# IO-testing-mezzanine.net
KiCad netlist of a schematic drawn in Altium Designer
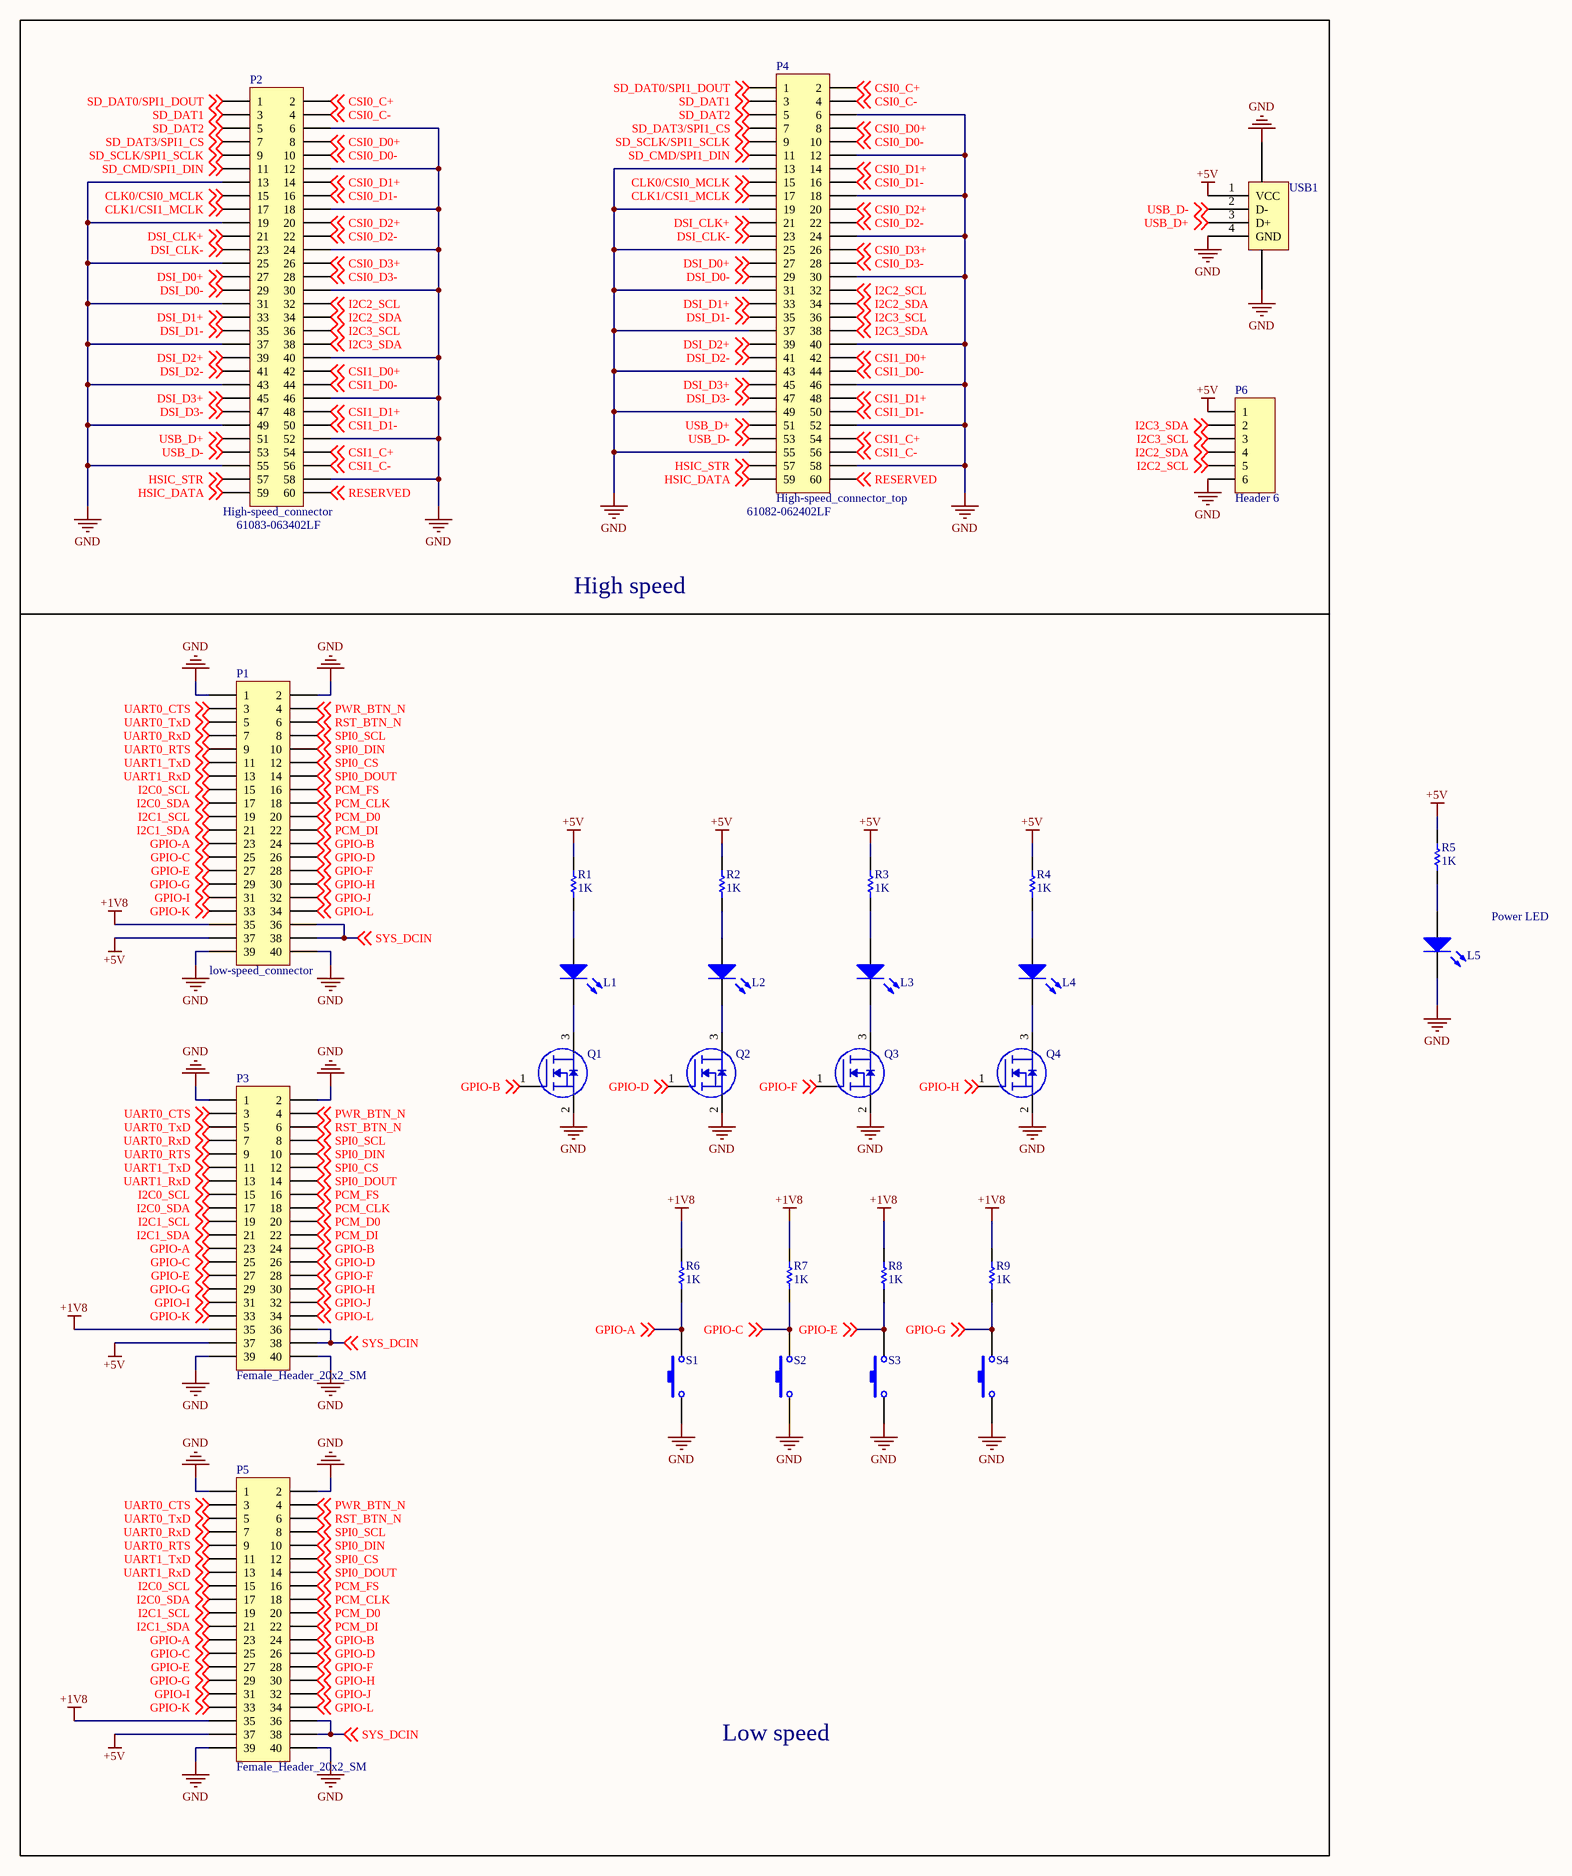
[diagram p0: IO-testing-mezzanine.SchDoc]

(export (version "E")
  (design (tool "Eeschema 10.0.6"))
  (components
    (comp (ref "L1")
      (value "~")
      (footprint "LED_0603")
      (description "LED BLUE CLEAR 0603 SMD")
      (fields
        (field (name "MANUFACTURER") "Lite-On Inc.")
        (field (name "MANUFACTURER PART NUMBER") "LTST-C193TBKT-5A")
      )
      (libsource (lib "IO-testing-mezzanine") (part "LTST-C193TBKT-5A"))
    )
    (comp (ref "L2")
      (value "~")
      (footprint "LED_0603")
      (description "LED BLUE CLEAR 0603 SMD")
      (fields
        (field (name "MANUFACTURER") "Lite-On Inc.")
        (field (name "MANUFACTURER PART NUMBER") "LTST-C193TBKT-5A")
      )
      (libsource (lib "IO-testing-mezzanine") (part "LTST-C193TBKT-5A"))
    )
    (comp (ref "L3")
      (value "~")
      (footprint "LED_0603")
      (description "LED BLUE CLEAR 0603 SMD")
      (fields
        (field (name "MANUFACTURER") "Lite-On Inc.")
        (field (name "MANUFACTURER PART NUMBER") "LTST-C193TBKT-5A")
      )
      (libsource (lib "IO-testing-mezzanine") (part "LTST-C193TBKT-5A"))
    )
    (comp (ref "L4")
      (value "~")
      (footprint "LED_0603")
      (description "LED BLUE CLEAR 0603 SMD")
      (fields
        (field (name "MANUFACTURER") "Lite-On Inc.")
        (field (name "MANUFACTURER PART NUMBER") "LTST-C193TBKT-5A")
      )
      (libsource (lib "IO-testing-mezzanine") (part "LTST-C193TBKT-5A"))
    )
    (comp (ref "L5")
      (value "~")
      (footprint "LED_0603")
      (description "LED BLUE CLEAR 0603 SMD")
      (fields
        (field (name "MANUFACTURER") "Lite-On Inc.")
        (field (name "MANUFACTURER PART NUMBER") "LTST-C193TBKT-5A")
      )
      (libsource (lib "IO-testing-mezzanine") (part "LTST-C193TBKT-5A"))
    )
    (comp (ref "P1")
      (value "low-speed_connector")
      (footprint "low-speed_connector_SM")
      (libsource (lib "mezza") (part "low-speed_connector"))
    )
    (comp (ref "P2")
      (value "High-speed_connector")
      (footprint "high-speed_connector")
      (fields (field (name "PARTNUMBER") "61083-063402LF"))
      (libsource (lib "mezza") (part "High-speed_connector"))
    )
    (comp (ref "P3")
      (value "Female_Header_20x2_SM")
      (footprint "Female_Header_20x2_SM")
      (libsource (lib "IO-testing-mezzanine") (part "Female_Header_20x2_SM"))
    )
    (comp (ref "P4")
      (value "High-speed_connector_top")
      (footprint "high-speed_connector_top")
      (fields
        (field (name "MANUFACTURER") "Amphenol FCI")
        (field (name "MANUFACTURER PART NUMBER") "61082-062402LF")
        (field (name "PARTNUMBER") "61082-062402LF")
      )
      (libsource (lib "IO-testing-mezzanine") (part "High-speed_connector_top"))
    )
    (comp (ref "P5")
      (value "Female_Header_20x2_SM")
      (footprint "low-speed_connector_SM_top")
      (libsource (lib "IO-testing-mezzanine") (part "Female_Header_20x2_SM"))
    )
    (comp (ref "P6")
      (value "Header 6")
      (footprint "HDR1X6")
      (description "Header, 6-Pin")
      (fields (field (name "PUBLISHER") "Altium Limited"))
      (libsource (lib "Miscellaneous Connectors") (part "Header 6"))
    )
    (comp (ref "Q1")
      (value "RUM002N05T2L")
      (footprint "SOT-723")
      (description "Nch 50V 200mA MOSFET")
      (libsource (lib "IO-testing-mezzanine") (part "RUM002N05T2L"))
    )
    (comp (ref "Q2")
      (value "RUM002N05T2L")
      (footprint "SOT-723")
      (description "Nch 50V 200mA MOSFET")
      (libsource (lib "IO-testing-mezzanine") (part "RUM002N05T2L"))
    )
    (comp (ref "Q3")
      (value "RUM002N05T2L")
      (footprint "SOT-723")
      (description "Nch 50V 200mA MOSFET")
      (libsource (lib "IO-testing-mezzanine") (part "RUM002N05T2L"))
    )
    (comp (ref "Q4")
      (value "RUM002N05T2L")
      (footprint "SOT-723")
      (description "Nch 50V 200mA MOSFET")
      (libsource (lib "IO-testing-mezzanine") (part "RUM002N05T2L"))
    )
    (comp (ref "R1")
      (value "1K")
      (footprint "0603")
      (description "Resistor")
      (fields
        (field (name "PARTNUMBER") "RC0603JR-071KL")
        (field (name "Comment") "Res1")
        (field (name "PUBLISHER") "Altium Limited")
      )
      (libsource (lib "IO-testing-mezzanine") (part "Res1"))
    )
    (comp (ref "R2")
      (value "1K")
      (footprint "0603")
      (description "Resistor")
      (fields
        (field (name "PARTNUMBER") "RC0603JR-071KL")
        (field (name "Comment") "Res1")
        (field (name "PUBLISHER") "Altium Limited")
      )
      (libsource (lib "IO-testing-mezzanine") (part "Res1"))
    )
    (comp (ref "R3")
      (value "1K")
      (footprint "0603")
      (description "Resistor")
      (fields
        (field (name "PARTNUMBER") "RC0603JR-071KL")
        (field (name "Comment") "Res1")
        (field (name "PUBLISHER") "Altium Limited")
      )
      (libsource (lib "IO-testing-mezzanine") (part "Res1"))
    )
    (comp (ref "R4")
      (value "1K")
      (footprint "0603")
      (description "Resistor")
      (fields
        (field (name "PARTNUMBER") "RC0603JR-071KL")
        (field (name "Comment") "Res1")
        (field (name "PUBLISHER") "Altium Limited")
      )
      (libsource (lib "IO-testing-mezzanine") (part "Res1"))
    )
    (comp (ref "R5")
      (value "1K")
      (footprint "0603")
      (description "Resistor")
      (fields
        (field (name "PARTNUMBER") "RC0603JR-071KL")
        (field (name "Comment") "Res1")
        (field (name "PUBLISHER") "Altium Limited")
      )
      (libsource (lib "IO-testing-mezzanine") (part "Res1"))
    )
    (comp (ref "R6")
      (value "1K")
      (footprint "0603")
      (description "Resistor")
      (fields
        (field (name "PARTNUMBER") "RC0603JR-071KL")
        (field (name "Comment") "Res1")
        (field (name "PUBLISHER") "Altium Limited")
      )
      (libsource (lib "IO-testing-mezzanine") (part "Res1"))
    )
    (comp (ref "R7")
      (value "1K")
      (footprint "0603")
      (description "Resistor")
      (fields
        (field (name "PARTNUMBER") "RC0603JR-071KL")
        (field (name "Comment") "Res1")
        (field (name "PUBLISHER") "Altium Limited")
      )
      (libsource (lib "IO-testing-mezzanine") (part "Res1"))
    )
    (comp (ref "R8")
      (value "1K")
      (footprint "0603")
      (description "Resistor")
      (fields
        (field (name "PARTNUMBER") "RC0603JR-071KL")
        (field (name "Comment") "Res1")
        (field (name "PUBLISHER") "Altium Limited")
      )
      (libsource (lib "IO-testing-mezzanine") (part "Res1"))
    )
    (comp (ref "R9")
      (value "1K")
      (footprint "0603")
      (description "Resistor")
      (fields
        (field (name "PARTNUMBER") "RC0603JR-071KL")
        (field (name "Comment") "Res1")
        (field (name "PUBLISHER") "Altium Limited")
      )
      (libsource (lib "IO-testing-mezzanine") (part "Res1"))
    )
    (comp (ref "S1")
      (value "SW-PB")
      (footprint "SW-PB")
      (description "Switch")
      (fields
        (field (name "MANUFACTURER") "C&K")
        (field (name "MANUFACTURER PART NUMBER") "KSR223GLFG")
        (field (name "PUBLISHER") "Altium Limited")
      )
      (libsource (lib "IO-testing-mezzanine") (part "SW-PB"))
    )
    (comp (ref "S2")
      (value "SW-PB")
      (footprint "SW-PB")
      (description "Switch")
      (fields
        (field (name "MANUFACTURER") "C&K")
        (field (name "MANUFACTURER PART NUMBER") "KSR223GLFG")
        (field (name "PUBLISHER") "Altium Limited")
      )
      (libsource (lib "IO-testing-mezzanine") (part "SW-PB"))
    )
    (comp (ref "S3")
      (value "SW-PB")
      (footprint "SW-PB")
      (description "Switch")
      (fields
        (field (name "MANUFACTURER") "C&K")
        (field (name "MANUFACTURER PART NUMBER") "KSR223GLFG")
        (field (name "PUBLISHER") "Altium Limited")
      )
      (libsource (lib "IO-testing-mezzanine") (part "SW-PB"))
    )
    (comp (ref "S4")
      (value "SW-PB")
      (footprint "SW-PB")
      (description "Switch")
      (fields
        (field (name "MANUFACTURER") "C&K")
        (field (name "MANUFACTURER PART NUMBER") "KSR223GLFG")
        (field (name "PUBLISHER") "Altium Limited")
      )
      (libsource (lib "IO-testing-mezzanine") (part "SW-PB"))
    )
    (comp (ref "USB1")
      (value "USB")
      (footprint "USB_a")
      (fields (field (name "PARTNUMBER") "USB-A-S-F-W-SM2") (field (name "MANUFACTURER") "Samtec Inc."))
      (libsource (lib "IO-testing-mezzanine") (part "USB"))
    )
  )
  (nets
    (net (code "1") (name "+1V8") (class "Default")
      (node (ref "P1") (pin "35") (pinfunction "35_35") (pintype "passive"))
      (node (ref "P3") (pin "35") (pinfunction "35_35") (pintype "passive"))
      (node (ref "P5") (pin "35") (pinfunction "35_35") (pintype "passive"))
      (node (ref "R6") (pin "2") (pinfunction "2_2") (pintype "passive"))
      (node (ref "R7") (pin "2") (pinfunction "2_2") (pintype "passive"))
      (node (ref "R8") (pin "2") (pinfunction "2_2") (pintype "passive"))
      (node (ref "R9") (pin "2") (pinfunction "2_2") (pintype "passive"))
    )
    (net (code "2") (name "+5V") (class "Default")
      (node (ref "P1") (pin "37") (pinfunction "37_37") (pintype "passive"))
      (node (ref "P3") (pin "37") (pinfunction "37_37") (pintype "passive"))
      (node (ref "P5") (pin "37") (pinfunction "37_37") (pintype "passive"))
      (node (ref "P6") (pin "1") (pinfunction "1_1") (pintype "passive"))
      (node (ref "R1") (pin "2") (pinfunction "2_2") (pintype "passive"))
      (node (ref "R2") (pin "2") (pinfunction "2_2") (pintype "passive"))
      (node (ref "R3") (pin "2") (pinfunction "2_2") (pintype "passive"))
      (node (ref "R4") (pin "2") (pinfunction "2_2") (pintype "passive"))
      (node (ref "R5") (pin "2") (pinfunction "2_2") (pintype "passive"))
      (node (ref "USB1") (pin "1") (pinfunction "VCC_1") (pintype "power_in"))
    )
    (net (code "3") (name "CLK0{slash}CSI0_MCLK") (class "Default")
      (node (ref "P2") (pin "15") (pinfunction "15_15") (pintype "passive"))
      (node (ref "P4") (pin "15") (pinfunction "15_15") (pintype "passive"))
    )
    (net (code "4") (name "CLK1{slash}CSI1_MCLK") (class "Default")
      (node (ref "P2") (pin "17") (pinfunction "17_17") (pintype "passive"))
      (node (ref "P4") (pin "17") (pinfunction "17_17") (pintype "passive"))
    )
    (net (code "5") (name "CSI0_C+") (class "Default")
      (node (ref "P2") (pin "2") (pinfunction "2_2") (pintype "passive"))
      (node (ref "P4") (pin "2") (pinfunction "2_2") (pintype "passive"))
    )
    (net (code "6") (name "CSI0_C-") (class "Default")
      (node (ref "P2") (pin "4") (pinfunction "4_4") (pintype "passive"))
      (node (ref "P4") (pin "4") (pinfunction "4_4") (pintype "passive"))
    )
    (net (code "7") (name "CSI0_D0+") (class "Default")
      (node (ref "P2") (pin "8") (pinfunction "8_8") (pintype "passive"))
      (node (ref "P4") (pin "8") (pinfunction "8_8") (pintype "passive"))
    )
    (net (code "8") (name "CSI0_D0-") (class "Default")
      (node (ref "P2") (pin "10") (pinfunction "10_10") (pintype "passive"))
      (node (ref "P4") (pin "10") (pinfunction "10_10") (pintype "passive"))
    )
    (net (code "9") (name "CSI0_D1+") (class "Default")
      (node (ref "P2") (pin "14") (pinfunction "14_14") (pintype "passive"))
      (node (ref "P4") (pin "14") (pinfunction "14_14") (pintype "passive"))
    )
    (net (code "10") (name "CSI0_D1-") (class "Default")
      (node (ref "P2") (pin "16") (pinfunction "16_16") (pintype "passive"))
      (node (ref "P4") (pin "16") (pinfunction "16_16") (pintype "passive"))
    )
    (net (code "11") (name "CSI0_D2+") (class "Default")
      (node (ref "P2") (pin "20") (pinfunction "20_20") (pintype "passive"))
      (node (ref "P4") (pin "20") (pinfunction "20_20") (pintype "passive"))
    )
    (net (code "12") (name "CSI0_D2-") (class "Default")
      (node (ref "P2") (pin "22") (pinfunction "22_22") (pintype "passive"))
      (node (ref "P4") (pin "22") (pinfunction "22_22") (pintype "passive"))
    )
    (net (code "13") (name "CSI0_D3+") (class "Default")
      (node (ref "P2") (pin "26") (pinfunction "26_26") (pintype "passive"))
      (node (ref "P4") (pin "26") (pinfunction "26_26") (pintype "passive"))
    )
    (net (code "14") (name "CSI0_D3-") (class "Default")
      (node (ref "P2") (pin "28") (pinfunction "28_28") (pintype "passive"))
      (node (ref "P4") (pin "28") (pinfunction "28_28") (pintype "passive"))
    )
    (net (code "15") (name "CSI1_C+") (class "Default")
      (node (ref "P2") (pin "54") (pinfunction "54_54") (pintype "passive"))
      (node (ref "P4") (pin "54") (pinfunction "54_54") (pintype "passive"))
    )
    (net (code "16") (name "CSI1_C-") (class "Default")
      (node (ref "P2") (pin "56") (pinfunction "56_56") (pintype "passive"))
      (node (ref "P4") (pin "56") (pinfunction "56_56") (pintype "passive"))
    )
    (net (code "17") (name "CSI1_D0+") (class "Default")
      (node (ref "P2") (pin "42") (pinfunction "42_42") (pintype "passive"))
      (node (ref "P4") (pin "42") (pinfunction "42_42") (pintype "passive"))
    )
    (net (code "18") (name "CSI1_D0-") (class "Default")
      (node (ref "P2") (pin "44") (pinfunction "44_44") (pintype "passive"))
      (node (ref "P4") (pin "44") (pinfunction "44_44") (pintype "passive"))
    )
    (net (code "19") (name "CSI1_D1+") (class "Default")
      (node (ref "P2") (pin "48") (pinfunction "48_48") (pintype "passive"))
      (node (ref "P4") (pin "48") (pinfunction "48_48") (pintype "passive"))
    )
    (net (code "20") (name "CSI1_D1-") (class "Default")
      (node (ref "P2") (pin "50") (pinfunction "50_50") (pintype "passive"))
      (node (ref "P4") (pin "50") (pinfunction "50_50") (pintype "passive"))
    )
    (net (code "21") (name "DSI_CLK+") (class "Default")
      (node (ref "P2") (pin "21") (pinfunction "21_21") (pintype "passive"))
      (node (ref "P4") (pin "21") (pinfunction "21_21") (pintype "passive"))
    )
    (net (code "22") (name "DSI_CLK-") (class "Default")
      (node (ref "P2") (pin "23") (pinfunction "23_23") (pintype "passive"))
      (node (ref "P4") (pin "23") (pinfunction "23_23") (pintype "passive"))
    )
    (net (code "23") (name "DSI_D0+") (class "Default")
      (node (ref "P2") (pin "27") (pinfunction "27_27") (pintype "passive"))
      (node (ref "P4") (pin "27") (pinfunction "27_27") (pintype "passive"))
    )
    (net (code "24") (name "DSI_D0-") (class "Default")
      (node (ref "P2") (pin "29") (pinfunction "29_29") (pintype "passive"))
      (node (ref "P4") (pin "29") (pinfunction "29_29") (pintype "passive"))
    )
    (net (code "25") (name "DSI_D1+") (class "Default")
      (node (ref "P2") (pin "33") (pinfunction "33_33") (pintype "passive"))
      (node (ref "P4") (pin "33") (pinfunction "33_33") (pintype "passive"))
    )
    (net (code "26") (name "DSI_D1-") (class "Default")
      (node (ref "P2") (pin "35") (pinfunction "35_35") (pintype "passive"))
      (node (ref "P4") (pin "35") (pinfunction "35_35") (pintype "passive"))
    )
    (net (code "27") (name "DSI_D2+") (class "Default")
      (node (ref "P2") (pin "39") (pinfunction "39_39") (pintype "passive"))
      (node (ref "P4") (pin "39") (pinfunction "39_39") (pintype "passive"))
    )
    (net (code "28") (name "DSI_D2-") (class "Default")
      (node (ref "P2") (pin "41") (pinfunction "41_41") (pintype "passive"))
      (node (ref "P4") (pin "41") (pinfunction "41_41") (pintype "passive"))
    )
    (net (code "29") (name "DSI_D3+") (class "Default")
      (node (ref "P2") (pin "45") (pinfunction "45_45") (pintype "passive"))
      (node (ref "P4") (pin "45") (pinfunction "45_45") (pintype "passive"))
    )
    (net (code "30") (name "DSI_D3-") (class "Default")
      (node (ref "P2") (pin "47") (pinfunction "47_47") (pintype "passive"))
      (node (ref "P4") (pin "47") (pinfunction "47_47") (pintype "passive"))
    )
    (net (code "31") (name "GND") (class "Default")
      (node (ref "L5") (pin "2") (pinfunction "K_2") (pintype "passive"))
      (node (ref "P1") (pin "1") (pinfunction "1_1") (pintype "passive"))
      (node (ref "P1") (pin "2") (pinfunction "2_2") (pintype "passive"))
      (node (ref "P1") (pin "39") (pinfunction "39_39") (pintype "passive"))
      (node (ref "P1") (pin "40") (pinfunction "40_40") (pintype "passive"))
      (node (ref "P2") (pin "12") (pinfunction "12_12") (pintype "passive"))
      (node (ref "P2") (pin "13") (pinfunction "13_13") (pintype "passive"))
      (node (ref "P2") (pin "18") (pinfunction "18_18") (pintype "passive"))
      (node (ref "P2") (pin "19") (pinfunction "19_19") (pintype "passive"))
      (node (ref "P2") (pin "24") (pinfunction "24_24") (pintype "passive"))
      (node (ref "P2") (pin "25") (pinfunction "25_25") (pintype "passive"))
      (node (ref "P2") (pin "30") (pinfunction "30_30") (pintype "passive"))
      (node (ref "P2") (pin "31") (pinfunction "31_31") (pintype "passive"))
      (node (ref "P2") (pin "37") (pinfunction "37_37") (pintype "passive"))
      (node (ref "P2") (pin "40") (pinfunction "40_40") (pintype "passive"))
      (node (ref "P2") (pin "43") (pinfunction "43_43") (pintype "passive"))
      (node (ref "P2") (pin "46") (pinfunction "46_46") (pintype "passive"))
      (node (ref "P2") (pin "49") (pinfunction "49_49") (pintype "passive"))
      (node (ref "P2") (pin "52") (pinfunction "52_52") (pintype "passive"))
      (node (ref "P2") (pin "55") (pinfunction "55_55") (pintype "passive"))
      (node (ref "P2") (pin "58") (pinfunction "58_58") (pintype "passive"))
      (node (ref "P2") (pin "6") (pinfunction "6_6") (pintype "passive"))
      (node (ref "P3") (pin "1") (pinfunction "1_1") (pintype "passive"))
      (node (ref "P3") (pin "2") (pinfunction "2_2") (pintype "passive"))
      (node (ref "P3") (pin "39") (pinfunction "39_39") (pintype "passive"))
      (node (ref "P3") (pin "40") (pinfunction "40_40") (pintype "passive"))
      (node (ref "P4") (pin "12") (pinfunction "12_12") (pintype "passive"))
      (node (ref "P4") (pin "13") (pinfunction "13_13") (pintype "passive"))
      (node (ref "P4") (pin "18") (pinfunction "18_18") (pintype "passive"))
      (node (ref "P4") (pin "19") (pinfunction "19_19") (pintype "passive"))
      (node (ref "P4") (pin "24") (pinfunction "24_24") (pintype "passive"))
      (node (ref "P4") (pin "25") (pinfunction "25_25") (pintype "passive"))
      (node (ref "P4") (pin "30") (pinfunction "30_30") (pintype "passive"))
      (node (ref "P4") (pin "31") (pinfunction "31_31") (pintype "passive"))
      (node (ref "P4") (pin "37") (pinfunction "37_37") (pintype "passive"))
      (node (ref "P4") (pin "40") (pinfunction "40_40") (pintype "passive"))
      (node (ref "P4") (pin "43") (pinfunction "43_43") (pintype "passive"))
      (node (ref "P4") (pin "46") (pinfunction "46_46") (pintype "passive"))
      (node (ref "P4") (pin "49") (pinfunction "49_49") (pintype "passive"))
      (node (ref "P4") (pin "52") (pinfunction "52_52") (pintype "passive"))
      (node (ref "P4") (pin "55") (pinfunction "55_55") (pintype "passive"))
      (node (ref "P4") (pin "58") (pinfunction "58_58") (pintype "passive"))
      (node (ref "P4") (pin "6") (pinfunction "6_6") (pintype "passive"))
      (node (ref "P5") (pin "1") (pinfunction "1_1") (pintype "passive"))
      (node (ref "P5") (pin "2") (pinfunction "2_2") (pintype "passive"))
      (node (ref "P5") (pin "39") (pinfunction "39_39") (pintype "passive"))
      (node (ref "P5") (pin "40") (pinfunction "40_40") (pintype "passive"))
      (node (ref "P6") (pin "6") (pinfunction "6_6") (pintype "passive"))
      (node (ref "Q1") (pin "2") (pinfunction "S_2") (pintype "passive"))
      (node (ref "Q2") (pin "2") (pinfunction "S_2") (pintype "passive"))
      (node (ref "Q3") (pin "2") (pinfunction "S_2") (pintype "passive"))
      (node (ref "Q4") (pin "2") (pinfunction "S_2") (pintype "passive"))
      (node (ref "S1") (pin "1") (pinfunction "1_1") (pintype "passive"))
      (node (ref "S2") (pin "1") (pinfunction "1_1") (pintype "passive"))
      (node (ref "S3") (pin "1") (pinfunction "1_1") (pintype "passive"))
      (node (ref "S4") (pin "1") (pinfunction "1_1") (pintype "passive"))
      (node (ref "USB1") (pin "4") (pinfunction "GND_4") (pintype "power_in"))
      (node (ref "USB1") (pin "5") (pinfunction "GND_5") (pintype "power_in"))
      (node (ref "USB1") (pin "6") (pinfunction "GND_6") (pintype "power_in"))
    )
    (net (code "32") (name "GPIO-A") (class "Default")
      (node (ref "P1") (pin "23") (pinfunction "23_23") (pintype "passive"))
      (node (ref "P3") (pin "23") (pinfunction "23_23") (pintype "passive"))
      (node (ref "P5") (pin "23") (pinfunction "23_23") (pintype "passive"))
      (node (ref "R6") (pin "1") (pinfunction "1_1") (pintype "passive"))
      (node (ref "S1") (pin "2") (pinfunction "2_2") (pintype "passive"))
    )
    (net (code "33") (name "GPIO-B") (class "Default")
      (node (ref "P1") (pin "24") (pinfunction "24_24") (pintype "passive"))
      (node (ref "P3") (pin "24") (pinfunction "24_24") (pintype "passive"))
      (node (ref "P5") (pin "24") (pinfunction "24_24") (pintype "passive"))
      (node (ref "Q1") (pin "1") (pinfunction "G_1") (pintype "passive"))
    )
    (net (code "34") (name "GPIO-C") (class "Default")
      (node (ref "P1") (pin "25") (pinfunction "25_25") (pintype "passive"))
      (node (ref "P3") (pin "25") (pinfunction "25_25") (pintype "passive"))
      (node (ref "P5") (pin "25") (pinfunction "25_25") (pintype "passive"))
      (node (ref "R7") (pin "1") (pinfunction "1_1") (pintype "passive"))
      (node (ref "S2") (pin "2") (pinfunction "2_2") (pintype "passive"))
    )
    (net (code "35") (name "GPIO-D") (class "Default")
      (node (ref "P1") (pin "26") (pinfunction "26_26") (pintype "passive"))
      (node (ref "P3") (pin "26") (pinfunction "26_26") (pintype "passive"))
      (node (ref "P5") (pin "26") (pinfunction "26_26") (pintype "passive"))
      (node (ref "Q2") (pin "1") (pinfunction "G_1") (pintype "passive"))
    )
    (net (code "36") (name "GPIO-E") (class "Default")
      (node (ref "P1") (pin "27") (pinfunction "27_27") (pintype "passive"))
      (node (ref "P3") (pin "27") (pinfunction "27_27") (pintype "passive"))
      (node (ref "P5") (pin "27") (pinfunction "27_27") (pintype "passive"))
      (node (ref "R8") (pin "1") (pinfunction "1_1") (pintype "passive"))
      (node (ref "S3") (pin "2") (pinfunction "2_2") (pintype "passive"))
    )
    (net (code "37") (name "GPIO-F") (class "Default")
      (node (ref "P1") (pin "28") (pinfunction "28_28") (pintype "passive"))
      (node (ref "P3") (pin "28") (pinfunction "28_28") (pintype "passive"))
      (node (ref "P5") (pin "28") (pinfunction "28_28") (pintype "passive"))
      (node (ref "Q3") (pin "1") (pinfunction "G_1") (pintype "passive"))
    )
    (net (code "38") (name "GPIO-G") (class "Default")
      (node (ref "P1") (pin "29") (pinfunction "29_29") (pintype "passive"))
      (node (ref "P3") (pin "29") (pinfunction "29_29") (pintype "passive"))
      (node (ref "P5") (pin "29") (pinfunction "29_29") (pintype "passive"))
      (node (ref "R9") (pin "1") (pinfunction "1_1") (pintype "passive"))
      (node (ref "S4") (pin "2") (pinfunction "2_2") (pintype "passive"))
    )
    (net (code "39") (name "GPIO-H") (class "Default")
      (node (ref "P1") (pin "30") (pinfunction "30_30") (pintype "passive"))
      (node (ref "P3") (pin "30") (pinfunction "30_30") (pintype "passive"))
      (node (ref "P5") (pin "30") (pinfunction "30_30") (pintype "passive"))
      (node (ref "Q4") (pin "1") (pinfunction "G_1") (pintype "passive"))
    )
    (net (code "40") (name "GPIO-I") (class "Default")
      (node (ref "P1") (pin "31") (pinfunction "31_31") (pintype "passive"))
      (node (ref "P3") (pin "31") (pinfunction "31_31") (pintype "passive"))
      (node (ref "P5") (pin "31") (pinfunction "31_31") (pintype "passive"))
    )
    (net (code "41") (name "GPIO-J") (class "Default")
      (node (ref "P1") (pin "32") (pinfunction "32_32") (pintype "passive"))
      (node (ref "P3") (pin "32") (pinfunction "32_32") (pintype "passive"))
      (node (ref "P5") (pin "32") (pinfunction "32_32") (pintype "passive"))
    )
    (net (code "42") (name "GPIO-K") (class "Default")
      (node (ref "P1") (pin "33") (pinfunction "33_33") (pintype "passive"))
      (node (ref "P3") (pin "33") (pinfunction "33_33") (pintype "passive"))
      (node (ref "P5") (pin "33") (pinfunction "33_33") (pintype "passive"))
    )
    (net (code "43") (name "GPIO-L") (class "Default")
      (node (ref "P1") (pin "34") (pinfunction "34_34") (pintype "passive"))
      (node (ref "P3") (pin "34") (pinfunction "34_34") (pintype "passive"))
      (node (ref "P5") (pin "34") (pinfunction "34_34") (pintype "passive"))
    )
    (net (code "44") (name "HSIC_DATA") (class "Default")
      (node (ref "P2") (pin "59") (pinfunction "59_59") (pintype "passive"))
      (node (ref "P4") (pin "59") (pinfunction "59_59") (pintype "passive"))
    )
    (net (code "45") (name "HSIC_STR") (class "Default")
      (node (ref "P2") (pin "39") (pinfunction "57_39") (pintype "passive"))
      (node (ref "P4") (pin "39") (pinfunction "57_39") (pintype "passive"))
    )
    (net (code "46") (name "I2C0_SCL") (class "Default")
      (node (ref "P1") (pin "15") (pinfunction "15_15") (pintype "passive"))
      (node (ref "P3") (pin "15") (pinfunction "15_15") (pintype "passive"))
      (node (ref "P5") (pin "15") (pinfunction "15_15") (pintype "passive"))
    )
    (net (code "47") (name "I2C0_SDA") (class "Default")
      (node (ref "P1") (pin "17") (pinfunction "17_17") (pintype "passive"))
      (node (ref "P3") (pin "17") (pinfunction "17_17") (pintype "passive"))
      (node (ref "P5") (pin "17") (pinfunction "17_17") (pintype "passive"))
    )
    (net (code "48") (name "I2C1_SCL") (class "Default")
      (node (ref "P1") (pin "19") (pinfunction "19_19") (pintype "passive"))
      (node (ref "P3") (pin "19") (pinfunction "19_19") (pintype "passive"))
      (node (ref "P5") (pin "19") (pinfunction "19_19") (pintype "passive"))
    )
    (net (code "49") (name "I2C1_SDA") (class "Default")
      (node (ref "P1") (pin "21") (pinfunction "21_21") (pintype "passive"))
      (node (ref "P3") (pin "21") (pinfunction "21_21") (pintype "passive"))
      (node (ref "P5") (pin "21") (pinfunction "21_21") (pintype "passive"))
    )
    (net (code "50") (name "I2C2_SCL") (class "Default")
      (node (ref "P2") (pin "32") (pinfunction "32_32") (pintype "passive"))
      (node (ref "P4") (pin "32") (pinfunction "32_32") (pintype "passive"))
      (node (ref "P6") (pin "5") (pinfunction "5_5") (pintype "passive"))
    )
    (net (code "51") (name "I2C2_SDA") (class "Default")
      (node (ref "P2") (pin "34") (pinfunction "34_34") (pintype "passive"))
      (node (ref "P4") (pin "34") (pinfunction "34_34") (pintype "passive"))
      (node (ref "P6") (pin "4") (pinfunction "4_4") (pintype "passive"))
    )
    (net (code "52") (name "I2C3_SCL") (class "Default")
      (node (ref "P2") (pin "36") (pinfunction "36_36") (pintype "passive"))
      (node (ref "P4") (pin "36") (pinfunction "36_36") (pintype "passive"))
      (node (ref "P6") (pin "3") (pinfunction "3_3") (pintype "passive"))
    )
    (net (code "53") (name "I2C3_SDA") (class "Default")
      (node (ref "P2") (pin "38") (pinfunction "38_38") (pintype "passive"))
      (node (ref "P4") (pin "38") (pinfunction "38_38") (pintype "passive"))
      (node (ref "P6") (pin "2") (pinfunction "2_2") (pintype "passive"))
    )
    (net (code "54") (name "Net-(L1-A)") (class "Default")
      (node (ref "L1") (pin "1") (pinfunction "A_1") (pintype "passive"))
      (node (ref "R1") (pin "1") (pinfunction "1_1") (pintype "passive"))
    )
    (net (code "55") (name "Net-(L1-K)") (class "Default")
      (node (ref "L1") (pin "2") (pinfunction "K_2") (pintype "passive"))
      (node (ref "Q1") (pin "3") (pinfunction "D_3") (pintype "passive"))
    )
    (net (code "56") (name "Net-(L2-A)") (class "Default")
      (node (ref "L2") (pin "1") (pinfunction "A_1") (pintype "passive"))
      (node (ref "R2") (pin "1") (pinfunction "1_1") (pintype "passive"))
    )
    (net (code "57") (name "Net-(L2-K)") (class "Default")
      (node (ref "L2") (pin "2") (pinfunction "K_2") (pintype "passive"))
      (node (ref "Q2") (pin "3") (pinfunction "D_3") (pintype "passive"))
    )
    (net (code "58") (name "Net-(L3-A)") (class "Default")
      (node (ref "L3") (pin "1") (pinfunction "A_1") (pintype "passive"))
      (node (ref "R3") (pin "1") (pinfunction "1_1") (pintype "passive"))
    )
    (net (code "59") (name "Net-(L3-K)") (class "Default")
      (node (ref "L3") (pin "2") (pinfunction "K_2") (pintype "passive"))
      (node (ref "Q3") (pin "3") (pinfunction "D_3") (pintype "passive"))
    )
    (net (code "60") (name "Net-(L4-A)") (class "Default")
      (node (ref "L4") (pin "1") (pinfunction "A_1") (pintype "passive"))
      (node (ref "R4") (pin "1") (pinfunction "1_1") (pintype "passive"))
    )
    (net (code "61") (name "Net-(L4-K)") (class "Default")
      (node (ref "L4") (pin "2") (pinfunction "K_2") (pintype "passive"))
      (node (ref "Q4") (pin "3") (pinfunction "D_3") (pintype "passive"))
    )
    (net (code "62") (name "Net-(L5-A)") (class "Default")
      (node (ref "L5") (pin "1") (pinfunction "A_1") (pintype "passive"))
      (node (ref "R5") (pin "1") (pinfunction "1_1") (pintype "passive"))
    )
    (net (code "63") (name "PCM_CLK") (class "Default")
      (node (ref "P1") (pin "18") (pinfunction "18_18") (pintype "passive"))
      (node (ref "P3") (pin "18") (pinfunction "18_18") (pintype "passive"))
      (node (ref "P5") (pin "18") (pinfunction "18_18") (pintype "passive"))
    )
    (net (code "64") (name "PCM_D0") (class "Default")
      (node (ref "P1") (pin "20") (pinfunction "20_20") (pintype "passive"))
      (node (ref "P3") (pin "20") (pinfunction "20_20") (pintype "passive"))
      (node (ref "P5") (pin "20") (pinfunction "20_20") (pintype "passive"))
    )
    (net (code "65") (name "PCM_DI") (class "Default")
      (node (ref "P1") (pin "22") (pinfunction "22_22") (pintype "passive"))
      (node (ref "P3") (pin "22") (pinfunction "22_22") (pintype "passive"))
      (node (ref "P5") (pin "22") (pinfunction "22_22") (pintype "passive"))
    )
    (net (code "66") (name "PCM_FS") (class "Default")
      (node (ref "P1") (pin "16") (pinfunction "16_16") (pintype "passive"))
      (node (ref "P3") (pin "16") (pinfunction "16_16") (pintype "passive"))
      (node (ref "P5") (pin "16") (pinfunction "16_16") (pintype "passive"))
    )
    (net (code "67") (name "PWR_BTN_N") (class "Default")
      (node (ref "P1") (pin "4") (pinfunction "4_4") (pintype "passive"))
      (node (ref "P3") (pin "4") (pinfunction "4_4") (pintype "passive"))
      (node (ref "P5") (pin "4") (pinfunction "4_4") (pintype "passive"))
    )
    (net (code "68") (name "RESERVED") (class "Default")
      (node (ref "P2") (pin "38") (pinfunction "60_38") (pintype "passive"))
      (node (ref "P4") (pin "38") (pinfunction "60_38") (pintype "passive"))
    )
    (net (code "69") (name "RST_BTN_N") (class "Default")
      (node (ref "P1") (pin "6") (pinfunction "6_6") (pintype "passive"))
      (node (ref "P3") (pin "6") (pinfunction "6_6") (pintype "passive"))
      (node (ref "P5") (pin "6") (pinfunction "6_6") (pintype "passive"))
    )
    (net (code "70") (name "SD_CMD{slash}SPI1_DIN") (class "Default")
      (node (ref "P2") (pin "11") (pinfunction "11_11") (pintype "passive"))
      (node (ref "P4") (pin "11") (pinfunction "11_11") (pintype "passive"))
    )
    (net (code "71") (name "SD_DAT0{slash}SPI1_DOUT") (class "Default")
      (node (ref "P2") (pin "1") (pinfunction "1_1") (pintype "passive"))
      (node (ref "P4") (pin "1") (pinfunction "1_1") (pintype "passive"))
    )
    (net (code "72") (name "SD_DAT1") (class "Default")
      (node (ref "P2") (pin "3") (pinfunction "3_3") (pintype "passive"))
      (node (ref "P4") (pin "3") (pinfunction "3_3") (pintype "passive"))
    )
    (net (code "73") (name "SD_DAT2") (class "Default")
      (node (ref "P2") (pin "5") (pinfunction "5_5") (pintype "passive"))
      (node (ref "P4") (pin "5") (pinfunction "5_5") (pintype "passive"))
    )
    (net (code "74") (name "SD_DAT3{slash}SPI1_CS") (class "Default")
      (node (ref "P2") (pin "7") (pinfunction "7_7") (pintype "passive"))
      (node (ref "P4") (pin "7") (pinfunction "7_7") (pintype "passive"))
    )
    (net (code "75") (name "SD_SCLK{slash}SPI1_SCLK") (class "Default")
      (node (ref "P2") (pin "9") (pinfunction "9_9") (pintype "passive"))
      (node (ref "P4") (pin "9") (pinfunction "9_9") (pintype "passive"))
    )
    (net (code "76") (name "SPI0_CS") (class "Default")
      (node (ref "P1") (pin "12") (pinfunction "12_12") (pintype "passive"))
      (node (ref "P3") (pin "12") (pinfunction "12_12") (pintype "passive"))
      (node (ref "P5") (pin "12") (pinfunction "12_12") (pintype "passive"))
    )
    (net (code "77") (name "SPI0_DIN") (class "Default")
      (node (ref "P1") (pin "10") (pinfunction "10_10") (pintype "passive"))
      (node (ref "P3") (pin "10") (pinfunction "10_10") (pintype "passive"))
      (node (ref "P5") (pin "10") (pinfunction "10_10") (pintype "passive"))
    )
    (net (code "78") (name "SPI0_DOUT") (class "Default")
      (node (ref "P1") (pin "14") (pinfunction "14_14") (pintype "passive"))
      (node (ref "P3") (pin "14") (pinfunction "14_14") (pintype "passive"))
      (node (ref "P5") (pin "14") (pinfunction "14_14") (pintype "passive"))
    )
    (net (code "79") (name "SPI0_SCL") (class "Default")
      (node (ref "P1") (pin "8") (pinfunction "8_8") (pintype "passive"))
      (node (ref "P3") (pin "8") (pinfunction "8_8") (pintype "passive"))
      (node (ref "P5") (pin "8") (pinfunction "8_8") (pintype "passive"))
    )
    (net (code "80") (name "SYS_DCIN") (class "Default")
      (node (ref "P1") (pin "36") (pinfunction "36_36") (pintype "passive"))
      (node (ref "P1") (pin "38") (pinfunction "38_38") (pintype "passive"))
      (node (ref "P3") (pin "36") (pinfunction "36_36") (pintype "passive"))
      (node (ref "P3") (pin "38") (pinfunction "38_38") (pintype "passive"))
      (node (ref "P5") (pin "36") (pinfunction "36_36") (pintype "passive"))
      (node (ref "P5") (pin "38") (pinfunction "38_38") (pintype "passive"))
    )
    (net (code "81") (name "UART0_CTS") (class "Default")
      (node (ref "P1") (pin "3") (pinfunction "3_3") (pintype "passive"))
      (node (ref "P3") (pin "3") (pinfunction "3_3") (pintype "passive"))
      (node (ref "P5") (pin "3") (pinfunction "3_3") (pintype "passive"))
    )
    (net (code "82") (name "UART0_RTS") (class "Default")
      (node (ref "P1") (pin "9") (pinfunction "9_9") (pintype "passive"))
      (node (ref "P3") (pin "9") (pinfunction "9_9") (pintype "passive"))
      (node (ref "P5") (pin "9") (pinfunction "9_9") (pintype "passive"))
    )
    (net (code "83") (name "UART0_RxD") (class "Default")
      (node (ref "P1") (pin "7") (pinfunction "7_7") (pintype "passive"))
      (node (ref "P3") (pin "7") (pinfunction "7_7") (pintype "passive"))
      (node (ref "P5") (pin "7") (pinfunction "7_7") (pintype "passive"))
    )
    (net (code "84") (name "UART0_TxD") (class "Default")
      (node (ref "P1") (pin "5") (pinfunction "5_5") (pintype "passive"))
      (node (ref "P3") (pin "5") (pinfunction "5_5") (pintype "passive"))
      (node (ref "P5") (pin "5") (pinfunction "5_5") (pintype "passive"))
    )
    (net (code "85") (name "UART1_RxD") (class "Default")
      (node (ref "P1") (pin "13") (pinfunction "13_13") (pintype "passive"))
      (node (ref "P3") (pin "13") (pinfunction "13_13") (pintype "passive"))
      (node (ref "P5") (pin "13") (pinfunction "13_13") (pintype "passive"))
    )
    (net (code "86") (name "UART1_TxD") (class "Default")
      (node (ref "P1") (pin "11") (pinfunction "11_11") (pintype "passive"))
      (node (ref "P3") (pin "11") (pinfunction "11_11") (pintype "passive"))
      (node (ref "P5") (pin "11") (pinfunction "11_11") (pintype "passive"))
    )
    (net (code "87") (name "USB_D+") (class "Default")
      (node (ref "P2") (pin "51") (pinfunction "51_51") (pintype "passive"))
      (node (ref "P4") (pin "51") (pinfunction "51_51") (pintype "passive"))
      (node (ref "USB1") (pin "3") (pinfunction "D+_3") (pintype "passive"))
    )
    (net (code "88") (name "USB_D-") (class "Default")
      (node (ref "P2") (pin "53") (pinfunction "53_53") (pintype "passive"))
      (node (ref "P4") (pin "53") (pinfunction "53_53") (pintype "passive"))
      (node (ref "USB1") (pin "2") (pinfunction "D-_2") (pintype "passive"))
    )
  )
)
